# Power.net
KiCad netlist of a schematic drawn in Altium Designer
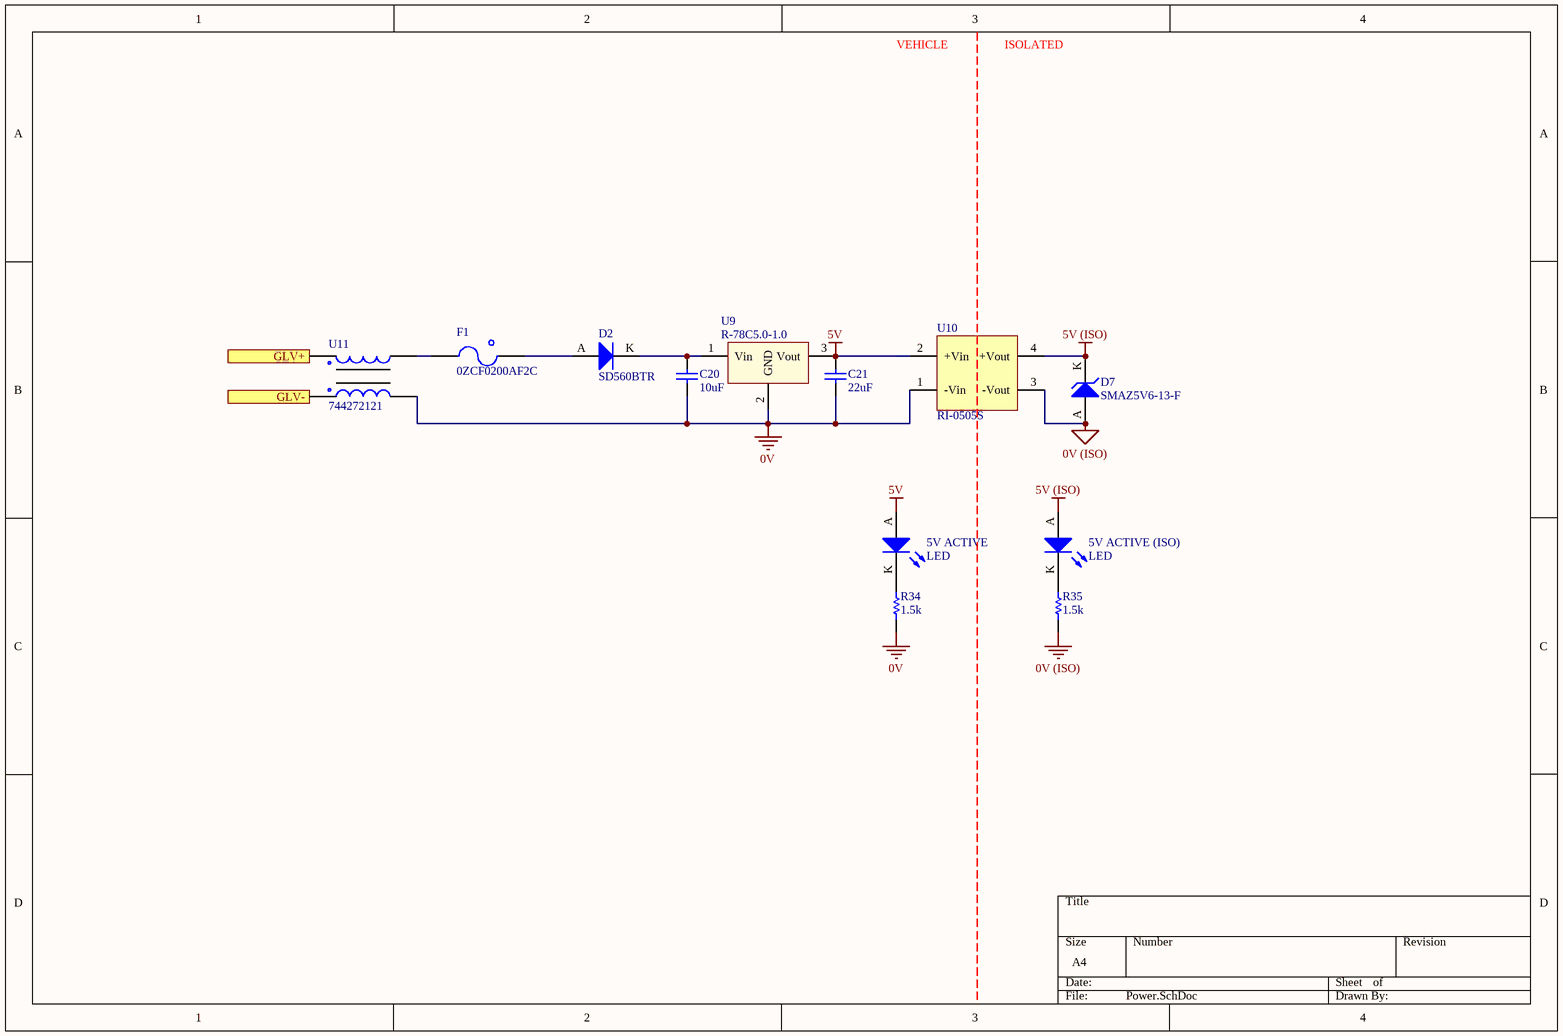
[diagram p0: Power.SchDoc]

(export (version "E")
  (design (tool "Eeschema 10.0.6"))
  (components
    (comp (ref "5V ACTIVE")
      (value "LED")
      (footprint "0805 LED")
      (description "Red LED Indication - Discrete 1.75V 0805 (2012 Metric)")
      (fields (field (name "MANUFACTURER") "ROHM Semiconductor") (field (name "PART NUMBER") "SML-210LTT86"))
      (libsource (lib "ts_19-standard-library") (part "LED"))
    )
    (comp (ref "5V ACTIVE (ISO)")
      (value "LED")
      (footprint "0805 LED")
      (description "Red LED Indication - Discrete 1.75V 0805 (2012 Metric)")
      (fields (field (name "MANUFACTURER") "ROHM Semiconductor") (field (name "PART NUMBER") "SML-210LTT86"))
      (libsource (lib "ts_19-standard-library") (part "LED"))
    )
    (comp (ref "C20")
      (value "10uF")
      (footprint "0805")
      (fields
        (field (name "TOLERANCE") "10%")
        (field (name "MANUFACTURER") "muRata")
        (field (name "DIGIKEY PART NUMBER") "490-10514-6-ND")
      )
      (libsource (lib "ts_19-standard-library") (part "Capacitor"))
    )
    (comp (ref "C21")
      (value "22uF")
      (footprint "0805")
      (fields
        (field (name "TOLERANCE") "20%")
        (field (name "MANUFACTURER") "muRata")
        (field (name "DIGIKEY PART NUMBER") "490-10511-1-ND")
      )
      (libsource (lib "ts_19-standard-library") (part "Capacitor"))
    )
    (comp (ref "D2")
      (value "SD560BTR")
      (footprint "SMB Diode")
      (description "1.2V_F 600V 5A SMB")
      (fields
        (field (name "MANUFACTURER") "SMC Diode Solutions")
        (field (name "DIGIKEY PART NUMBER") "1655-1530-2-ND")
      )
      (libsource (lib "ts_19-standard-library") (part "Diode"))
    )
    (comp (ref "D7")
      (value "SMAZ5V6-13-F")
      (footprint "DI SMA Diode")
      (description "DIODE ZENER 5.6V 1W SMA")
      (fields
        (field (name "MANUFACTURER") "Diodes Inc")
        (field (name "DIGIKEY PART NUMBER") "SMAZ5V6-FDICT-ND")
      )
      (libsource (lib "ts_19-standard-library") (part "Zener Diode"))
    )
    (comp (ref "F1")
      (value "0ZCF0200AF2C")
      (footprint "2920")
      (description "SMD 24V 2A Fuse")
      (fields
        (field (name "MANUFACTURER") "Bel Fuse Inc")
        (field (name "DIGIKEY PART NUMBER") "507-1749-2-ND")
      )
      (libsource (lib "ts_19-standard-library") (part "PTC Fuse"))
    )
    (comp (ref "R34")
      (value "1.5k")
      (footprint "0805")
      (fields
        (field (name "MANUFACTURER") "YAGEO")
        (field (name "PART NUMBER") "RC0805FR071K5L")
        (field (name "TOLERANCE") "0.01")
      )
      (libsource (lib "ts_19-standard-library") (part "Resistor"))
    )
    (comp (ref "R35")
      (value "1.5k")
      (footprint "0805")
      (fields
        (field (name "MANUFACTURER") "YAGEO")
        (field (name "PART NUMBER") "RC0805FR071K5L")
        (field (name "TOLERANCE") "0.01")
      )
      (libsource (lib "ts_19-standard-library") (part "Resistor"))
    )
    (comp (ref "U9")
      (value "R-78C5.0-1.0")
      (footprint "RECOM 3-SIP")
      (description "CONV DC/DC 1A 5V OUT SIP VERT")
      (fields (field (name "MANUFACTURER") "Recom") (field (name "DIGIKEY PART NUMBER") "945-1395-5-ND"))
      (libsource (lib "ts_19-standard-library") (part "R-78C5.0-1.0"))
    )
    (comp (ref "U10")
      (value "RI-0505S")
      (footprint "RECOM 4-SIP")
      (description "5V DC-DC Converter (2W)")
      (fields (field (name "MANUFACTURER") "Recom") (field (name "DIGIKEY PART NUMBER") "945-1189-ND"))
      (libsource (lib "ts_19-standard-library") (part "RI-0505S"))
    )
    (comp (ref "U11")
      (value "744272121")
      (footprint "Wurth 4-PC Pad")
      (description "Common Mode Choke 120UH 2.5A 2LN 460 OHM SMD")
      (fields
        (field (name "MANUFACTURER") "Wurth Electronics Inc")
        (field (name "DIGIKEY PART NUMBER") "732-1489-2-ND")
      )
      (libsource (lib "ts_19-standard-library") (part "744272121"))
    )
  )
  (nets
    (net (code "1") (name "/GLV+") (class "Default")
      (node (ref "U11") (pin "1") (pinfunction "1_1") (pintype "passive"))
    )
    (net (code "2") (name "/GLV-") (class "Default")
      (node (ref "U11") (pin "4") (pinfunction "4_4") (pintype "passive"))
    )
    (net (code "3") (name "0V") (class "Default")
      (node (ref "C20") (pin "1") (pinfunction "1_1") (pintype "passive"))
      (node (ref "C21") (pin "1") (pinfunction "1_1") (pintype "passive"))
      (node (ref "R34") (pin "1") (pinfunction "1_1") (pintype "passive"))
      (node (ref "U10") (pin "1") (pinfunction "-Vin_1") (pintype "power_in"))
      (node (ref "U11") (pin "3") (pinfunction "3_3") (pintype "power_in"))
      (node (ref "U9") (pin "2") (pinfunction "GND_2") (pintype "passive"))
    )
    (net (code "4") (name "0V (ISO)") (class "Default")
      (node (ref "D7") (pin "A") (pinfunction "A_A") (pintype "passive"))
      (node (ref "R35") (pin "1") (pinfunction "1_1") (pintype "passive"))
      (node (ref "U10") (pin "3") (pinfunction "-Vout_3") (pintype "power_in"))
    )
    (net (code "5") (name "5V") (class "Default")
      (node (ref "5V ACTIVE") (pin "A") (pinfunction "A_A") (pintype "passive"))
      (node (ref "C21") (pin "2") (pinfunction "2_2") (pintype "passive"))
      (node (ref "U10") (pin "2") (pinfunction "+Vin_2") (pintype "power_in"))
      (node (ref "U9") (pin "3") (pinfunction "Vout_3") (pintype "passive"))
    )
    (net (code "6") (name "5V (ISO)") (class "Default")
      (node (ref "5V ACTIVE (ISO)") (pin "A") (pinfunction "A_A") (pintype "passive"))
      (node (ref "D7") (pin "K") (pinfunction "K_K") (pintype "passive"))
      (node (ref "U10") (pin "4") (pinfunction "+Vout_4") (pintype "power_in"))
    )
    (net (code "7") (name "Net-(5V ACTIVE (ISO)-PadK)") (class "Default")
      (node (ref "5V ACTIVE (ISO)") (pin "K") (pinfunction "K_K") (pintype "passive"))
      (node (ref "R35") (pin "2") (pinfunction "2_2") (pintype "passive"))
    )
    (net (code "8") (name "Net-(5V ACTIVE-PadK)") (class "Default")
      (node (ref "5V ACTIVE") (pin "K") (pinfunction "K_K") (pintype "passive"))
      (node (ref "R34") (pin "2") (pinfunction "2_2") (pintype "passive"))
    )
    (net (code "9") (name "Net-(D2-PadA)") (class "Default")
      (node (ref "D2") (pin "A") (pinfunction "A_A") (pintype "passive"))
      (node (ref "F1") (pin "2") (pinfunction "2_2") (pintype "passive"))
    )
    (net (code "10") (name "Net-(F1-Pad1)") (class "Default")
      (node (ref "F1") (pin "1") (pinfunction "1_1") (pintype "passive"))
      (node (ref "U11") (pin "2") (pinfunction "2_2") (pintype "passive"))
    )
    (net (code "11") (name "Net-(U9-Vin)") (class "Default")
      (node (ref "C20") (pin "2") (pinfunction "2_2") (pintype "passive"))
      (node (ref "D2") (pin "K") (pinfunction "K_K") (pintype "passive"))
      (node (ref "U9") (pin "1") (pinfunction "Vin_1") (pintype "passive"))
    )
  )
)
